# DAWA-IRSENSOR-6_3.net
KiCad netlist of a schematic drawn in EAGLE
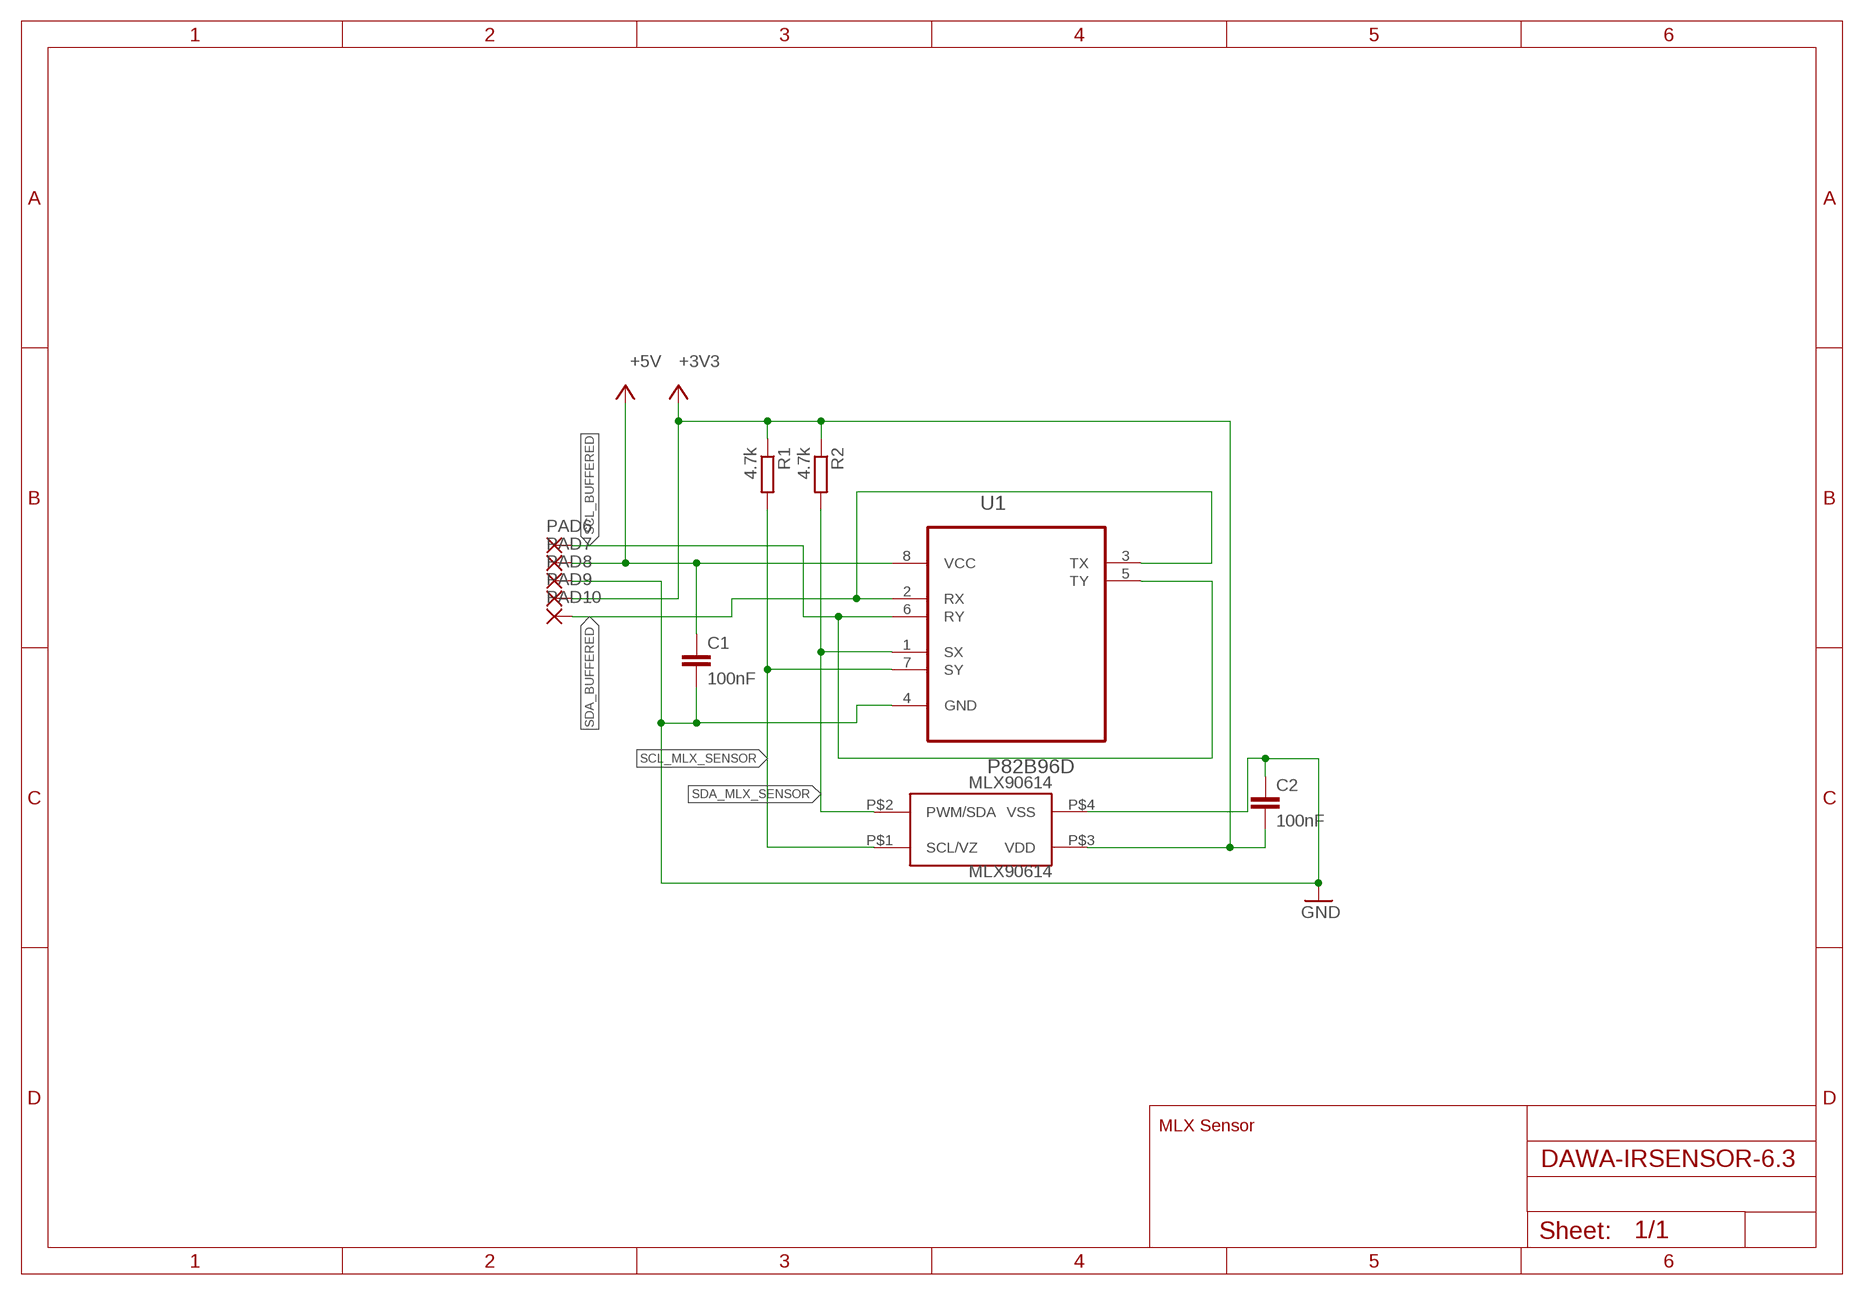
[diagram p0: schematic, sheet 1]

(export (version "E")
  (design (tool "Eeschema 10.0.6"))
  (components
    (comp (ref "C1")
      (value "100nF")
      (footprint "eagle-import:C0603")
      (libsource (lib "eagle-import") (part "C-EUC0603"))
    )
    (comp (ref "C2")
      (value "100nF")
      (footprint "eagle-import:C0603")
      (libsource (lib "eagle-import") (part "C-EUC0603"))
    )
    (comp (ref "MLX90614")
      (value "MLX90614")
      (footprint "eagle-import:TO-39")
      (libsource (lib "eagle-import") (part "MLX90614_"))
    )
    (comp (ref "PAD6")
      (value "WIREPAD1,6/0,9")
      (footprint "eagle-import:1,6_0,9")
      (libsource (lib "eagle-import") (part "WIREPAD1,6/0,9"))
    )
    (comp (ref "PAD7")
      (value "WIREPAD1,6/0,9")
      (footprint "eagle-import:1,6_0,9")
      (libsource (lib "eagle-import") (part "WIREPAD1,6/0,9"))
    )
    (comp (ref "PAD8")
      (value "WIREPAD1,6/0,9")
      (footprint "eagle-import:1,6_0,9")
      (libsource (lib "eagle-import") (part "WIREPAD1,6/0,9"))
    )
    (comp (ref "PAD9")
      (value "WIREPAD1,6/0,9")
      (footprint "eagle-import:1,6_0,9")
      (libsource (lib "eagle-import") (part "WIREPAD1,6/0,9"))
    )
    (comp (ref "PAD10")
      (value "WIREPAD1,6/0,9")
      (footprint "eagle-import:1,6_0,9")
      (libsource (lib "eagle-import") (part "WIREPAD1,6/0,9"))
    )
    (comp (ref "R1")
      (value "4.7k")
      (footprint "eagle-import:R0603")
      (libsource (lib "eagle-import") (part "R-EU_R0603"))
    )
    (comp (ref "R2")
      (value "4.7k")
      (footprint "eagle-import:R0603")
      (libsource (lib "eagle-import") (part "R-EU_R0603"))
    )
    (comp (ref "U1")
      (value "P82B96D")
      (footprint "eagle-import:SOIC127P600X175-8N")
      (libsource (lib "eagle-import") (part "P82B96D"))
    )
  )
  (nets
    (net (code "1") (name "+3V3") (class "Default")
      (node (ref "C2") (pin "2") (pinfunction "2_2") (pintype "passive"))
      (node (ref "MLX90614") (pin "P$3") (pinfunction "VDD_P$3") (pintype "bidirectional"))
      (node (ref "PAD9") (pin "1") (pinfunction "P_1") (pintype "passive"))
      (node (ref "R1") (pin "1") (pinfunction "1_1") (pintype "passive"))
      (node (ref "R2") (pin "1") (pinfunction "1_1") (pintype "passive"))
    )
    (net (code "2") (name "+5V") (class "Default")
      (node (ref "C1") (pin "1") (pinfunction "1_1") (pintype "passive"))
      (node (ref "PAD7") (pin "1") (pinfunction "P_1") (pintype "passive"))
      (node (ref "U1") (pin "8") (pinfunction "VCC_8") (pintype "power_in"))
    )
    (net (code "3") (name "GND") (class "Default")
      (node (ref "C1") (pin "2") (pinfunction "2_2") (pintype "passive"))
      (node (ref "C2") (pin "1") (pinfunction "1_1") (pintype "passive"))
      (node (ref "MLX90614") (pin "P$4") (pinfunction "VSS_P$4") (pintype "bidirectional"))
      (node (ref "PAD8") (pin "1") (pinfunction "P_1") (pintype "passive"))
      (node (ref "U1") (pin "4") (pinfunction "GND_4") (pintype "passive"))
    )
    (net (code "4") (name "SCL_BUFFERED") (class "Default")
      (node (ref "PAD6") (pin "1") (pinfunction "P_1") (pintype "passive"))
      (node (ref "U1") (pin "5") (pinfunction "TY_5") (pintype "output"))
      (node (ref "U1") (pin "6") (pinfunction "RY_6") (pintype "input"))
    )
    (net (code "5") (name "SCL_MLX_SENSOR") (class "Default")
      (node (ref "MLX90614") (pin "P$1") (pinfunction "SCL/VZ_P$1") (pintype "bidirectional"))
      (node (ref "R1") (pin "2") (pinfunction "2_2") (pintype "passive"))
      (node (ref "U1") (pin "7") (pinfunction "SY_7") (pintype "input"))
    )
    (net (code "6") (name "SDA_BUFFERED") (class "Default")
      (node (ref "PAD10") (pin "1") (pinfunction "P_1") (pintype "passive"))
      (node (ref "U1") (pin "2") (pinfunction "RX_2") (pintype "input"))
      (node (ref "U1") (pin "3") (pinfunction "TX_3") (pintype "output"))
    )
    (net (code "7") (name "SDA_MLX_SENSOR") (class "Default")
      (node (ref "MLX90614") (pin "P$2") (pinfunction "PWM/SDA_P$2") (pintype "bidirectional"))
      (node (ref "R2") (pin "2") (pinfunction "2_2") (pintype "passive"))
      (node (ref "U1") (pin "1") (pinfunction "SX_1") (pintype "input"))
    )
  )
)
